# ADC-SYNC_INPUT.net
KiCad netlist of a schematic drawn in Altium Designer
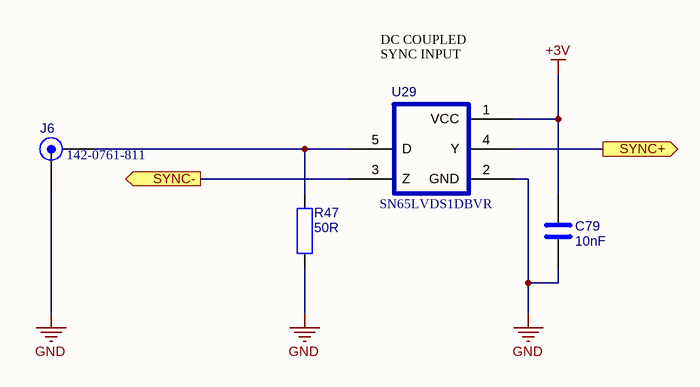
[diagram p0: ADC-SYNC INPUT.SchDoc]

(export (version "E")
  (design (tool "Eeschema 10.0.6"))
  (components
    (comp (ref "C79")
      (value "10nF")
      (footprint "CAPC1005X55N")
      (description "CAP SMD 0603")
      (fields
        (field (name "Comment") "Footprint ???")
        (field (name "CREATED_BY") "*")
        (field (name "CHECKED_BY") "*")
      )
      (libsource (lib "Abdus-TEMP") (part "CAP-0603"))
    )
    (comp (ref "J6")
      (value "~")
      (footprint "EDGE_LAUNCH_TH_SMA")
      (description "High Frequency SMA End Lauch Connector")
      (fields
        (field (name "MANUFACTURER") "JOHNSON")
        (field (name "VOLTAGE") "???")
        (field (name "MANUFACTURER_PN") "142-0761-811")
        (field (name "CREATED_BY") "CT")
        (field (name "CHECKED_BY") "*")
      )
      (libsource (lib "Charles-TEMP") (part "142-0761-811"))
    )
    (comp (ref "R47")
      (value "50R")
      (footprint "RESC1005X40N")
      (description "RESISTOR SMD 0805")
      (fields (field (name "CREATED_BY") "*") (field (name "CHECKED_BY") "NN"))
      (libsource (lib "EDA_Passive") (part "RES-0805"))
    )
    (comp (ref "U29")
      (value "SN65LVDS1DBVR")
      (footprint "SOT95P280X145-5N")
      (description "High Speed Differential Line Driver/Receiver")
      (fields
        (field (name "MANUFACTURER") "TI")
        (field (name "CREATED_BY") "IN")
        (field (name "CHECKED_BY") "*")
      )
      (libsource (lib "Ishvah-TEMP") (part "SN65LVDS1DBVR"))
    )
  )
  (nets
    (net (code "1") (name "+3V") (class "Default")
      (node (ref "C79") (pin "2") (pinfunction "2_2") (pintype "passive"))
      (node (ref "U29") (pin "1") (pinfunction "VCC_1") (pintype "passive"))
    )
    (net (code "2") (name "/SYNC+") (class "Default")
      (node (ref "U29") (pin "4") (pinfunction "Y_4") (pintype "passive"))
    )
    (net (code "3") (name "/SYNC-") (class "Default")
      (node (ref "U29") (pin "3") (pinfunction "Z_3") (pintype "passive"))
    )
    (net (code "4") (name "GND") (class "Default")
      (node (ref "C79") (pin "1") (pinfunction "1_1") (pintype "passive"))
      (node (ref "J6") (pin "2") (pinfunction "2_2") (pintype "passive"))
      (node (ref "R47") (pin "2") (pinfunction "2_2") (pintype "passive"))
      (node (ref "U29") (pin "2") (pinfunction "GND_2") (pintype "passive"))
    )
    (net (code "5") (name "Net-(U29-D)") (class "Default")
      (node (ref "J6") (pin "1") (pinfunction "1_1") (pintype "passive"))
      (node (ref "R47") (pin "1") (pinfunction "1_1") (pintype "passive"))
      (node (ref "U29") (pin "5") (pinfunction "D_5") (pintype "passive"))
    )
  )
)
